# galePCB2.net
KiCad netlist of a schematic drawn in EAGLE
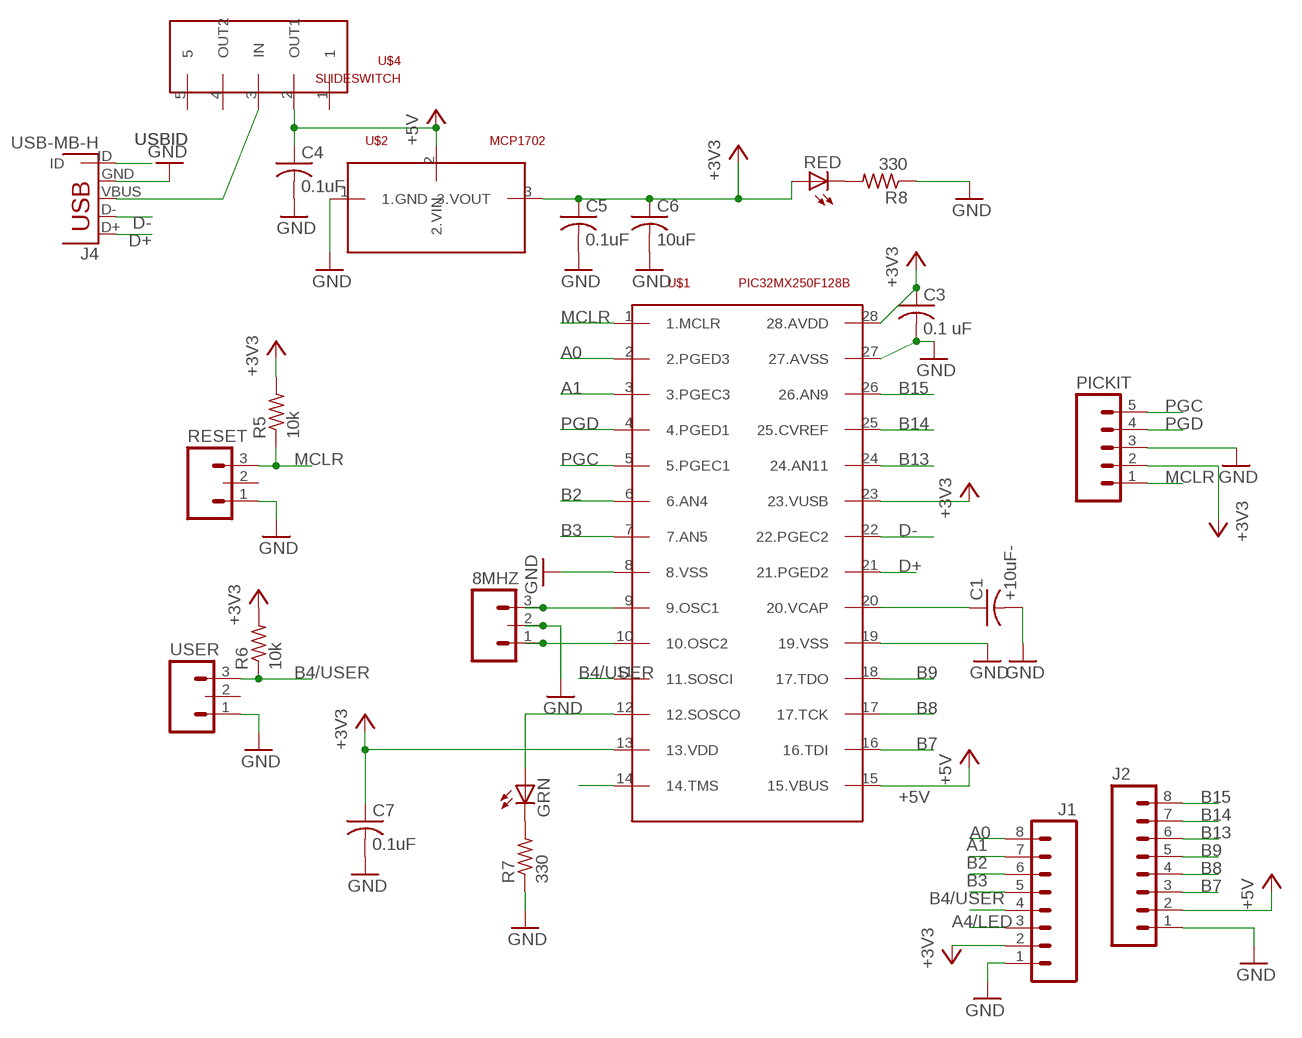
[diagram p0: schematic, sheet 1]

(export (version "E")
  (design (tool "Eeschema 10.0.6"))
  (components
    (comp (ref "8MHZ")
      (value "M03PTH")
      (footprint "eagle-import:1X03")
      (libsource (lib "eagle-import") (part "M03PTH"))
    )
    (comp (ref "C1")
      (value "+10uF-")
      (footprint "eagle-import:C025-024X044")
      (libsource (lib "eagle-import") (part "C-US025-024X044"))
    )
    (comp (ref "C3")
      (value "0.1 uF")
      (footprint "eagle-import:C025-024X044")
      (libsource (lib "eagle-import") (part "C-US025-024X044"))
    )
    (comp (ref "C4")
      (value "0.1uF")
      (footprint "eagle-import:C025-024X044")
      (libsource (lib "eagle-import") (part "C-US025-024X044"))
    )
    (comp (ref "C5")
      (value "0.1uF")
      (footprint "eagle-import:C025-024X044")
      (libsource (lib "eagle-import") (part "C-US025-024X044"))
    )
    (comp (ref "C6")
      (value "10uF")
      (footprint "eagle-import:C025-024X044")
      (libsource (lib "eagle-import") (part "C-US025-024X044"))
    )
    (comp (ref "C7")
      (value "0.1uF")
      (footprint "eagle-import:C025-024X044")
      (libsource (lib "eagle-import") (part "C-US025-024X044"))
    )
    (comp (ref "GRN")
      (value "LED3MM")
      (footprint "eagle-import:LED3MM")
      (libsource (lib "eagle-import") (part "LED3MM"))
    )
    (comp (ref "J1")
      (value "M08")
      (footprint "eagle-import:1X08_ROUND")
      (libsource (lib "eagle-import") (part "M08"))
    )
    (comp (ref "J2")
      (value "M08")
      (footprint "eagle-import:1X08_ROUND")
      (libsource (lib "eagle-import") (part "M08"))
    )
    (comp (ref "J4")
      (value "USB-MB-H")
      (footprint "eagle-import:USB-MB-H")
      (libsource (lib "eagle-import") (part "USB-MB-H"))
    )
    (comp (ref "PICKIT")
      (value "M05PTH")
      (footprint "eagle-import:1X05")
      (libsource (lib "eagle-import") (part "M05PTH"))
    )
    (comp (ref "R5")
      (value "10k")
      (footprint "eagle-import:0207_10")
      (libsource (lib "eagle-import") (part "R-US_0207/10"))
    )
    (comp (ref "R6")
      (value "10k")
      (footprint "eagle-import:0207_10")
      (libsource (lib "eagle-import") (part "R-US_0207/10"))
    )
    (comp (ref "R7")
      (value "330")
      (footprint "eagle-import:0207_10")
      (libsource (lib "eagle-import") (part "R-US_0207/10"))
    )
    (comp (ref "R8")
      (value "330")
      (footprint "eagle-import:0207_10")
      (libsource (lib "eagle-import") (part "R-US_0207/10"))
    )
    (comp (ref "RED")
      (value "LED3MM")
      (footprint "eagle-import:LED3MM")
      (libsource (lib "eagle-import") (part "LED3MM"))
    )
    (comp (ref "RESET")
      (value "M03LOCK")
      (footprint "eagle-import:1X03_LOCK")
      (libsource (lib "eagle-import") (part "M03LOCK"))
    )
    (comp (ref "U$1")
      (value "PIC32MX250F128B")
      (footprint "eagle-import:DIL28-3")
      (libsource (lib "eagle-import") (part "PIC32"))
    )
    (comp (ref "U$2")
      (value "MCP1702")
      (footprint "eagle-import:TO92")
      (libsource (lib "eagle-import") (part "MCP1702"))
    )
    (comp (ref "U$4")
      (value "SLIDESWITCH")
      (footprint "eagle-import:SLIDESWITCH")
      (libsource (lib "eagle-import") (part "SLIDESWITCH"))
    )
    (comp (ref "USER")
      (value "M03LOCK")
      (footprint "eagle-import:1X03_LOCK")
      (libsource (lib "eagle-import") (part "M03LOCK"))
    )
  )
  (nets
    (net (code "1") (name "+3V3") (class "Default")
      (node (ref "C3") (pin "1") (pinfunction "1_1") (pintype "passive"))
      (node (ref "C5") (pin "1") (pinfunction "1_1") (pintype "passive"))
      (node (ref "C6") (pin "1") (pinfunction "1_1") (pintype "passive"))
      (node (ref "C7") (pin "1") (pinfunction "1_1") (pintype "passive"))
      (node (ref "J1") (pin "2") (pinfunction "2_2") (pintype "passive"))
      (node (ref "PICKIT") (pin "2") (pinfunction "2_2") (pintype "passive"))
      (node (ref "R5") (pin "2") (pinfunction "2_2") (pintype "passive"))
      (node (ref "R6") (pin "2") (pinfunction "2_2") (pintype "passive"))
      (node (ref "RED") (pin "A") (pinfunction "A_A") (pintype "passive"))
      (node (ref "U$1") (pin "13") (pinfunction "13.VDD_13") (pintype "bidirectional"))
      (node (ref "U$1") (pin "23") (pinfunction "23.VUSB_23") (pintype "bidirectional"))
      (node (ref "U$1") (pin "28") (pinfunction "28.AVDD_28") (pintype "bidirectional"))
      (node (ref "U$2") (pin "3") (pinfunction "3.VOUT_3") (pintype "bidirectional"))
    )
    (net (code "2") (name "+5V") (class "Default")
      (node (ref "C4") (pin "1") (pinfunction "1_1") (pintype "passive"))
      (node (ref "J2") (pin "2") (pinfunction "2_2") (pintype "passive"))
      (node (ref "U$1") (pin "15") (pinfunction "15.VBUS_15") (pintype "bidirectional"))
      (node (ref "U$2") (pin "2") (pinfunction "2.VIN_2") (pintype "bidirectional"))
      (node (ref "U$4") (pin "2") (pinfunction "OUT1_2") (pintype "bidirectional"))
    )
    (net (code "3") (name "/A0") (class "Default")
      (node (ref "J1") (pin "8") (pinfunction "8_8") (pintype "passive"))
      (node (ref "U$1") (pin "2") (pinfunction "2.PGED3_2") (pintype "bidirectional"))
    )
    (net (code "4") (name "/A1") (class "Default")
      (node (ref "J1") (pin "7") (pinfunction "7_7") (pintype "passive"))
      (node (ref "U$1") (pin "3") (pinfunction "3.PGEC3_3") (pintype "bidirectional"))
    )
    (net (code "5") (name "/A4{slash}LED") (class "Default")
      (node (ref "GRN") (pin "A") (pinfunction "A_A") (pintype "passive"))
      (node (ref "J1") (pin "3") (pinfunction "3_3") (pintype "passive"))
      (node (ref "U$1") (pin "12") (pinfunction "12.SOSCO_12") (pintype "bidirectional"))
    )
    (net (code "6") (name "/B2") (class "Default")
      (node (ref "J1") (pin "6") (pinfunction "6_6") (pintype "passive"))
      (node (ref "U$1") (pin "6") (pinfunction "6.AN4_6") (pintype "bidirectional"))
    )
    (net (code "7") (name "/B3") (class "Default")
      (node (ref "J1") (pin "5") (pinfunction "5_5") (pintype "passive"))
      (node (ref "U$1") (pin "7") (pinfunction "7.AN5_7") (pintype "bidirectional"))
    )
    (net (code "8") (name "/B4{slash}USER") (class "Default")
      (node (ref "J1") (pin "4") (pinfunction "4_4") (pintype "passive"))
      (node (ref "R6") (pin "1") (pinfunction "1_1") (pintype "passive"))
      (node (ref "U$1") (pin "11") (pinfunction "11.SOSCI_11") (pintype "bidirectional"))
      (node (ref "USER") (pin "3") (pinfunction "3_3") (pintype "passive"))
    )
    (net (code "9") (name "/B7") (class "Default")
      (node (ref "J2") (pin "3") (pinfunction "3_3") (pintype "passive"))
      (node (ref "U$1") (pin "16") (pinfunction "16.TDI_16") (pintype "bidirectional"))
    )
    (net (code "10") (name "/B8") (class "Default")
      (node (ref "J2") (pin "4") (pinfunction "4_4") (pintype "passive"))
      (node (ref "U$1") (pin "17") (pinfunction "17.TCK_17") (pintype "bidirectional"))
    )
    (net (code "11") (name "/B9") (class "Default")
      (node (ref "J2") (pin "5") (pinfunction "5_5") (pintype "passive"))
      (node (ref "U$1") (pin "18") (pinfunction "17.TDO_18") (pintype "bidirectional"))
    )
    (net (code "12") (name "/B13") (class "Default")
      (node (ref "J2") (pin "6") (pinfunction "6_6") (pintype "passive"))
      (node (ref "U$1") (pin "24") (pinfunction "24.AN11_24") (pintype "bidirectional"))
    )
    (net (code "13") (name "/B14") (class "Default")
      (node (ref "J2") (pin "7") (pinfunction "7_7") (pintype "passive"))
      (node (ref "U$1") (pin "25") (pinfunction "25.CVREF_25") (pintype "bidirectional"))
    )
    (net (code "14") (name "/B15") (class "Default")
      (node (ref "J2") (pin "8") (pinfunction "8_8") (pintype "passive"))
      (node (ref "U$1") (pin "26") (pinfunction "26.AN9_26") (pintype "bidirectional"))
    )
    (net (code "15") (name "/D+") (class "Default")
      (node (ref "J4") (pin "D+") (pinfunction "D+_D+") (pintype "bidirectional"))
      (node (ref "U$1") (pin "21") (pinfunction "21.PGED2_21") (pintype "bidirectional"))
    )
    (net (code "16") (name "/D-") (class "Default")
      (node (ref "J4") (pin "D-") (pinfunction "D-_D-") (pintype "bidirectional"))
      (node (ref "U$1") (pin "22") (pinfunction "22.PGEC2_22") (pintype "bidirectional"))
    )
    (net (code "17") (name "/MCLR") (class "Default")
      (node (ref "PICKIT") (pin "1") (pinfunction "1_1") (pintype "passive"))
      (node (ref "R5") (pin "1") (pinfunction "1_1") (pintype "passive"))
      (node (ref "RESET") (pin "3") (pinfunction "3_3") (pintype "passive"))
      (node (ref "U$1") (pin "1") (pinfunction "1.MCLR_1") (pintype "bidirectional"))
    )
    (net (code "18") (name "/PGC") (class "Default")
      (node (ref "PICKIT") (pin "5") (pinfunction "5_5") (pintype "passive"))
      (node (ref "U$1") (pin "5") (pinfunction "5.PGEC1_5") (pintype "bidirectional"))
    )
    (net (code "19") (name "/PGD") (class "Default")
      (node (ref "PICKIT") (pin "4") (pinfunction "4_4") (pintype "passive"))
      (node (ref "U$1") (pin "4") (pinfunction "4.PGED1_4") (pintype "bidirectional"))
    )
    (net (code "20") (name "/USBID") (class "Default")
      (node (ref "J4") (pin "ID") (pinfunction "ID_ID") (pintype "bidirectional"))
      (node (ref "U$1") (pin "14") (pinfunction "14.TMS_14") (pintype "bidirectional"))
    )
    (net (code "21") (name "GND") (class "Default")
      (node (ref "8MHZ") (pin "2") (pinfunction "2_2") (pintype "passive"))
      (node (ref "C1") (pin "2") (pinfunction "2_2") (pintype "passive"))
      (node (ref "C3") (pin "2") (pinfunction "2_2") (pintype "passive"))
      (node (ref "C4") (pin "2") (pinfunction "2_2") (pintype "passive"))
      (node (ref "C5") (pin "2") (pinfunction "2_2") (pintype "passive"))
      (node (ref "C6") (pin "2") (pinfunction "2_2") (pintype "passive"))
      (node (ref "C7") (pin "2") (pinfunction "2_2") (pintype "passive"))
      (node (ref "J1") (pin "1") (pinfunction "1_1") (pintype "passive"))
      (node (ref "J2") (pin "1") (pinfunction "1_1") (pintype "passive"))
      (node (ref "J4") (pin "GND") (pinfunction "GND_GND") (pintype "bidirectional"))
      (node (ref "PICKIT") (pin "3") (pinfunction "3_3") (pintype "passive"))
      (node (ref "R7") (pin "1") (pinfunction "1_1") (pintype "passive"))
      (node (ref "R8") (pin "1") (pinfunction "1_1") (pintype "passive"))
      (node (ref "RESET") (pin "1") (pinfunction "1_1") (pintype "passive"))
      (node (ref "U$1") (pin "19") (pinfunction "19.VSS_19") (pintype "bidirectional"))
      (node (ref "U$1") (pin "27") (pinfunction "27.AVSS_27") (pintype "bidirectional"))
      (node (ref "U$1") (pin "8") (pinfunction "8.VSS_8") (pintype "bidirectional"))
      (node (ref "U$2") (pin "1") (pinfunction "1.GND_1") (pintype "bidirectional"))
      (node (ref "USER") (pin "1") (pinfunction "1_1") (pintype "passive"))
    )
    (net (code "22") (name "Net-(GRN-C)") (class "Default")
      (node (ref "GRN") (pin "K") (pinfunction "C_K") (pintype "passive"))
      (node (ref "R7") (pin "2") (pinfunction "2_2") (pintype "passive"))
    )
    (net (code "23") (name "Net-(RED-C)") (class "Default")
      (node (ref "R8") (pin "2") (pinfunction "2_2") (pintype "passive"))
      (node (ref "RED") (pin "K") (pinfunction "C_K") (pintype "passive"))
    )
    (net (code "24") (name "Net-(U$1-9.OSC1)") (class "Default")
      (node (ref "8MHZ") (pin "3") (pinfunction "3_3") (pintype "passive"))
      (node (ref "U$1") (pin "9") (pinfunction "9.OSC1_9") (pintype "bidirectional"))
    )
    (net (code "25") (name "Net-(U$1-10.OSC2)") (class "Default")
      (node (ref "8MHZ") (pin "1") (pinfunction "1_1") (pintype "passive"))
      (node (ref "U$1") (pin "10") (pinfunction "10.OSC2_10") (pintype "bidirectional"))
    )
    (net (code "26") (name "Net-(U$1-20.VCAP)") (class "Default")
      (node (ref "C1") (pin "1") (pinfunction "1_1") (pintype "passive"))
      (node (ref "U$1") (pin "20") (pinfunction "20.VCAP_20") (pintype "bidirectional"))
    )
    (net (code "27") (name "Net-(U$4-IN)") (class "Default")
      (node (ref "J4") (pin "VBUS") (pinfunction "VBUS_VBUS") (pintype "bidirectional"))
      (node (ref "U$4") (pin "3") (pinfunction "IN_3") (pintype "bidirectional"))
    )
    (net (code "28") (name "unconnected-(RESET-Pad2)") (class "Default")
      (node (ref "RESET") (pin "2") (pinfunction "2_2") (pintype "passive"))
    )
    (net (code "29") (name "unconnected-(U$4-OUT2-Pad4)") (class "Default")
      (node (ref "U$4") (pin "4") (pinfunction "OUT2_4") (pintype "bidirectional"))
    )
    (net (code "30") (name "unconnected-(U$4-Pad1)") (class "Default")
      (node (ref "U$4") (pin "1") (pinfunction "1_1") (pintype "bidirectional"))
    )
    (net (code "31") (name "unconnected-(U$4-Pad5)") (class "Default")
      (node (ref "U$4") (pin "5") (pinfunction "5_5") (pintype "bidirectional"))
    )
    (net (code "32") (name "unconnected-(USER-Pad2)") (class "Default")
      (node (ref "USER") (pin "2") (pinfunction "2_2") (pintype "passive"))
    )
  )
)
